# REGENIX_DRIVER_2.net
KiCad netlist of a schematic drawn in Altium Designer
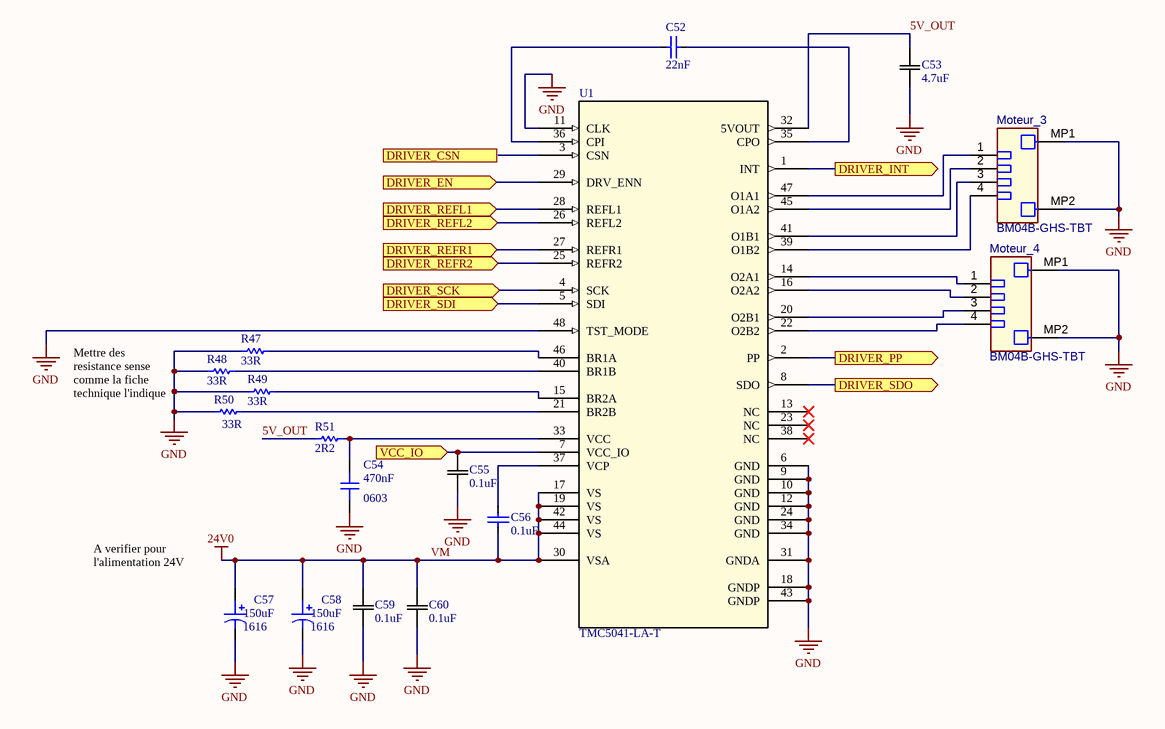
[diagram p0: REGENIX_DRIVER_2.SchDoc]

(export (version "E")
  (design (tool "Eeschema 10.0.6"))
  (components
    (comp (ref "C52")
      (value "22nF")
      (footprint "CAPACITOR-0603")
      (description "Capacitor-0603-0.22uF-25V-X7R")
      (libsource (lib "main_lib") (part "Capacitor-0603-0.22uF-25V-X7R"))
    )
    (comp (ref "C53")
      (value "4.7uF")
      (footprint "CAP_CL21_SAM")
      (description "CAP CER 4.7UF 25V X5R 0805  CL21A475KAQNNNE")
      (libsource (lib "CL21A475KAQNNNE") (part "CL21A475KAQNNNE"))
    )
    (comp (ref "C54")
      (value "470nF")
      (footprint "CAP_0603")
      (description "CAP - 0603")
      (fields (field (name "PACKAGE") "0603") (field (name "CREATEDBY") "Jonathan Bouchard"))
      (libsource (lib "S7CAS_LIB2023") (part "CAP - 0603"))
    )
    (comp (ref "C55")
      (value "0.1uF")
      (footprint "CAP_CL10_SAM")
      (description "CAP CER 0.1UF 50V X7R 0603 CL10B104KB8NNWC")
      (libsource (lib "CL10B104KB8NNWC") (part "CL10B104KB8NNWC"))
    )
    (comp (ref "C56")
      (value "0.1uF")
      (footprint "CAPACITOR-0603")
      (description "Capacitor-0603-0.22uF-25V-X7R")
      (libsource (lib "main_lib") (part "Capacitor-0603-0.22uF-25V-X7R"))
    )
    (comp (ref "C57")
      (value "150uF")
      (footprint "CAP_ALU_1616_vishay")
      (description "CAP - ALU 470uF 20% 50V - 1616")
      (fields
        (field (name "MFG") "Vishay Dale")
        (field (name "MFG PART NUMBER") "MAL214699108E3")
        (field (name "PACKAGE") "1616")
        (field (name "CREATEDBY") "Jonathan Bouchard")
      )
      (libsource (lib "S7CAS_LIB2023") (part "CAP_ALU_MAL214699108E3"))
    )
    (comp (ref "C58")
      (value "150uF")
      (footprint "CAP_ALU_1616_vishay")
      (description "CAP - ALU 470uF 20% 50V - 1616")
      (fields
        (field (name "MFG") "Vishay Dale")
        (field (name "MFG PART NUMBER") "MAL214699108E3")
        (field (name "PACKAGE") "1616")
        (field (name "CREATEDBY") "Jonathan Bouchard")
      )
      (libsource (lib "S7CAS_LIB2023") (part "CAP_ALU_MAL214699108E3"))
    )
    (comp (ref "C59")
      (value "0.1uF")
      (footprint "CAP_CL10_SAM")
      (description "CAP CER 0.1UF 50V X7R 0603 CL10B104KB8NNWC")
      (libsource (lib "CL10B104KB8NNWC") (part "CL10B104KB8NNWC"))
    )
    (comp (ref "C60")
      (value "0.1uF")
      (footprint "CAP_CL10_SAM")
      (description "CAP CER 0.1UF 50V X7R 0603 CL10B104KB8NNWC")
      (libsource (lib "CL10B104KB8NNWC") (part "CL10B104KB8NNWC"))
    )
    (comp (ref "Moteur_3")
      (value "BM04B-GHS-TBT")
      (footprint "JST-BM04B-GHS-TBT_V")
      (description "Header, Pitch 1.25 mm, 1 x 4 Position, Height 4.05 mm, -25 to 85 degC")
      (libsource (lib "Marylin Bechara") (part "CMP-00071-3"))
    )
    (comp (ref "Moteur_4")
      (value "BM04B-GHS-TBT")
      (footprint "JST-BM04B-GHS-TBT_V")
      (description "Header, Pitch 1.25 mm, 1 x 4 Position, Height 4.05 mm, -25 to 85 degC")
      (libsource (lib "Marylin Bechara") (part "CMP-00071-3"))
    )
    (comp (ref "R47")
      (value "33R")
      (footprint "RESISTOR-1206")
      (description "Resistor1206-33R")
      (fields (field (name "Comment") "SMT resistor"))
      (libsource (lib "main_lib") (part "Resistor1206-33R"))
    )
    (comp (ref "R48")
      (value "33R")
      (footprint "RESISTOR-1206")
      (description "Resistor1206-33R")
      (fields (field (name "Comment") "SMT resistor"))
      (libsource (lib "main_lib") (part "Resistor1206-33R"))
    )
    (comp (ref "R49")
      (value "33R")
      (footprint "RESISTOR-1206")
      (description "Resistor1206-33R")
      (fields (field (name "Comment") "SMT resistor"))
      (libsource (lib "main_lib") (part "Resistor1206-33R"))
    )
    (comp (ref "R50")
      (value "33R")
      (footprint "RESISTOR-1206")
      (description "Resistor1206-33R")
      (fields (field (name "Comment") "SMT resistor"))
      (libsource (lib "main_lib") (part "Resistor1206-33R"))
    )
    (comp (ref "R51")
      (value "2R2")
      (footprint "Resistor-0603")
      (description "Resistor0603-22R")
      (fields (field (name "Comment") "SMT resistor"))
      (libsource (lib "main_lib") (part "Resistor0603-22R"))
    )
    (comp (ref "U1")
      (value "TMC5041-LA-T")
      (footprint "QFN48_7X7_TRI")
      (description "No Description Available")
      (libsource (lib "TMC5041-LA-T") (part "TMC5041-LA-T"))
    )
  )
  (nets
    (net (code "1") (name "/5V_OUT") (class "Default")
      (node (ref "C53") (pin "2") (pinfunction "2_2") (pintype "passive"))
      (node (ref "R51") (pin "1") (pinfunction "1_1") (pintype "passive"))
      (node (ref "U1") (pin "32") (pinfunction "5VOUT_32") (pintype "output"))
    )
    (net (code "3") (name "/DRIVER_EN") (class "Default")
      (node (ref "U1") (pin "29") (pinfunction "DRV_ENN_29") (pintype "input"))
    )
    (net (code "4") (name "/DRIVER_INT") (class "Default")
      (node (ref "U1") (pin "1") (pinfunction "INT_1") (pintype "output"))
    )
    (net (code "5") (name "/DRIVER_PP") (class "Default")
      (node (ref "U1") (pin "2") (pinfunction "PP_2") (pintype "output"))
    )
    (net (code "6") (name "/DRIVER_REFL1") (class "Default")
      (node (ref "U1") (pin "28") (pinfunction "REFL1_28") (pintype "input"))
    )
    (net (code "7") (name "/DRIVER_REFL2") (class "Default")
      (node (ref "U1") (pin "26") (pinfunction "REFL2_26") (pintype "input"))
    )
    (net (code "8") (name "/DRIVER_REFR1") (class "Default")
      (node (ref "U1") (pin "27") (pinfunction "REFR1_27") (pintype "input"))
    )
    (net (code "9") (name "/DRIVER_REFR2") (class "Default")
      (node (ref "U1") (pin "25") (pinfunction "REFR2_25") (pintype "input"))
    )
    (net (code "10") (name "/DRIVER_SCK") (class "Default")
      (node (ref "U1") (pin "4") (pinfunction "SCK_4") (pintype "input"))
    )
    (net (code "11") (name "/DRIVER_SDI") (class "Default")
      (node (ref "U1") (pin "5") (pinfunction "SDI_5") (pintype "input"))
    )
    (net (code "12") (name "/DRIVER_SDO") (class "Default")
      (node (ref "U1") (pin "8") (pinfunction "SDO_8") (pintype "output"))
    )
    (net (code "13") (name "/VCC_IO") (class "Default")
      (node (ref "C55") (pin "2") (pinfunction "2_2") (pintype "passive"))
      (node (ref "U1") (pin "7") (pinfunction "VCC_IO_7") (pintype "power_in"))
    )
    (net (code "14") (name "24V0") (class "Default")
      (node (ref "C56") (pin "1") (pinfunction "1_1") (pintype "passive"))
      (node (ref "C57") (pin "1") (pinfunction "1_1") (pintype "passive"))
      (node (ref "C58") (pin "1") (pinfunction "1_1") (pintype "passive"))
      (node (ref "C59") (pin "2") (pinfunction "2_2") (pintype "passive"))
      (node (ref "C60") (pin "2") (pinfunction "2_2") (pintype "passive"))
      (node (ref "U1") (pin "17") (pinfunction "VS_17") (pintype "power_in"))
      (node (ref "U1") (pin "19") (pinfunction "VS_19") (pintype "power_in"))
      (node (ref "U1") (pin "30") (pinfunction "VSA_30") (pintype "power_in"))
      (node (ref "U1") (pin "42") (pinfunction "VS_42") (pintype "power_in"))
      (node (ref "U1") (pin "44") (pinfunction "VS_44") (pintype "power_in"))
    )
    (net (code "15") (name "GND") (class "Default")
      (node (ref "C53") (pin "1") (pinfunction "1_1") (pintype "passive"))
      (node (ref "C54") (pin "1") (pinfunction "1_1") (pintype "passive"))
      (node (ref "C55") (pin "1") (pinfunction "1_1") (pintype "passive"))
      (node (ref "C57") (pin "2") (pinfunction "2_2") (pintype "passive"))
      (node (ref "C58") (pin "2") (pinfunction "2_2") (pintype "passive"))
      (node (ref "C59") (pin "1") (pinfunction "1_1") (pintype "passive"))
      (node (ref "C60") (pin "1") (pinfunction "1_1") (pintype "passive"))
      (node (ref "Moteur_3") (pin "MP1") (pinfunction "MP1_MP1") (pintype "passive"))
      (node (ref "Moteur_3") (pin "MP2") (pinfunction "MP2_MP2") (pintype "passive"))
      (node (ref "Moteur_4") (pin "MP1") (pinfunction "MP1_MP1") (pintype "passive"))
      (node (ref "Moteur_4") (pin "MP2") (pinfunction "MP2_MP2") (pintype "passive"))
      (node (ref "R47") (pin "1") (pinfunction "1_1") (pintype "passive"))
      (node (ref "R48") (pin "1") (pinfunction "1_1") (pintype "passive"))
      (node (ref "R49") (pin "1") (pinfunction "1_1") (pintype "passive"))
      (node (ref "R50") (pin "1") (pinfunction "1_1") (pintype "passive"))
      (node (ref "U1") (pin "10") (pinfunction "GND_10") (pintype "power_in"))
      (node (ref "U1") (pin "11") (pinfunction "CLK_11") (pintype "input"))
      (node (ref "U1") (pin "12") (pinfunction "GND_12") (pintype "power_in"))
      (node (ref "U1") (pin "18") (pinfunction "GNDP_18") (pintype "power_in"))
      (node (ref "U1") (pin "24") (pinfunction "GND_24") (pintype "power_in"))
      (node (ref "U1") (pin "31") (pinfunction "GNDA_31") (pintype "power_in"))
      (node (ref "U1") (pin "34") (pinfunction "GND_34") (pintype "power_in"))
      (node (ref "U1") (pin "43") (pinfunction "GNDP_43") (pintype "power_in"))
      (node (ref "U1") (pin "48") (pinfunction "TST_MODE_48") (pintype "input"))
      (node (ref "U1") (pin "6") (pinfunction "GND_6") (pintype "power_in"))
      (node (ref "U1") (pin "9") (pinfunction "GND_9") (pintype "power_in"))
    )
    (net (code "16") (name "Net-(U1-BR1A)") (class "Default")
      (node (ref "R47") (pin "2") (pinfunction "2_2") (pintype "passive"))
      (node (ref "U1") (pin "46") (pinfunction "BR1A_46") (pintype "passive"))
    )
    (net (code "17") (name "Net-(U1-BR1B)") (class "Default")
      (node (ref "R48") (pin "2") (pinfunction "2_2") (pintype "passive"))
      (node (ref "U1") (pin "40") (pinfunction "BR1B_40") (pintype "passive"))
    )
    (net (code "18") (name "Net-(U1-BR2A)") (class "Default")
      (node (ref "R49") (pin "2") (pinfunction "2_2") (pintype "passive"))
      (node (ref "U1") (pin "15") (pinfunction "BR2A_15") (pintype "passive"))
    )
    (net (code "19") (name "Net-(U1-BR2B)") (class "Default")
      (node (ref "R50") (pin "2") (pinfunction "2_2") (pintype "passive"))
      (node (ref "U1") (pin "21") (pinfunction "BR2B_21") (pintype "passive"))
    )
    (net (code "20") (name "Net-(U1-CPI)") (class "Default")
      (node (ref "C52") (pin "1") (pinfunction "1_1") (pintype "passive"))
      (node (ref "U1") (pin "36") (pinfunction "CPI_36") (pintype "input"))
    )
    (net (code "21") (name "Net-(U1-CPO)") (class "Default")
      (node (ref "C52") (pin "2") (pinfunction "2_2") (pintype "passive"))
      (node (ref "U1") (pin "35") (pinfunction "CPO_35") (pintype "output"))
    )
    (net (code "22") (name "Net-(U1-O1A1)") (class "Default")
      (node (ref "Moteur_3") (pin "1") (pinfunction "1_1") (pintype "passive"))
      (node (ref "U1") (pin "47") (pinfunction "O1A1_47") (pintype "output"))
    )
    (net (code "23") (name "Net-(U1-O1A2)") (class "Default")
      (node (ref "Moteur_3") (pin "2") (pinfunction "2_2") (pintype "passive"))
      (node (ref "U1") (pin "45") (pinfunction "O1A2_45") (pintype "output"))
    )
    (net (code "24") (name "Net-(U1-O1B1)") (class "Default")
      (node (ref "Moteur_3") (pin "3") (pinfunction "3_3") (pintype "passive"))
      (node (ref "U1") (pin "41") (pinfunction "O1B1_41") (pintype "output"))
    )
    (net (code "25") (name "Net-(U1-O1B2)") (class "Default")
      (node (ref "Moteur_3") (pin "4") (pinfunction "4_4") (pintype "passive"))
      (node (ref "U1") (pin "39") (pinfunction "O1B2_39") (pintype "output"))
    )
    (net (code "26") (name "Net-(U1-O2A1)") (class "Default")
      (node (ref "Moteur_4") (pin "1") (pinfunction "1_1") (pintype "passive"))
      (node (ref "U1") (pin "14") (pinfunction "O2A1_14") (pintype "output"))
    )
    (net (code "27") (name "Net-(U1-O2A2)") (class "Default")
      (node (ref "Moteur_4") (pin "2") (pinfunction "2_2") (pintype "passive"))
      (node (ref "U1") (pin "16") (pinfunction "O2A2_16") (pintype "output"))
    )
    (net (code "28") (name "Net-(U1-O2B1)") (class "Default")
      (node (ref "Moteur_4") (pin "3") (pinfunction "3_3") (pintype "passive"))
      (node (ref "U1") (pin "20") (pinfunction "O2B1_20") (pintype "output"))
    )
    (net (code "29") (name "Net-(U1-O2B2)") (class "Default")
      (node (ref "Moteur_4") (pin "4") (pinfunction "4_4") (pintype "passive"))
      (node (ref "U1") (pin "22") (pinfunction "O2B2_22") (pintype "output"))
    )
    (net (code "30") (name "Net-(U1-VCC)") (class "Default")
      (node (ref "C54") (pin "2") (pinfunction "2_2") (pintype "passive"))
      (node (ref "R51") (pin "2") (pinfunction "2_2") (pintype "passive"))
      (node (ref "U1") (pin "33") (pinfunction "VCC_33") (pintype "power_in"))
    )
    (net (code "31") (name "Net-(U1-VCP)") (class "Default")
      (node (ref "C56") (pin "2") (pinfunction "2_2") (pintype "passive"))
      (node (ref "U1") (pin "37") (pinfunction "VCP_37") (pintype "power_in"))
    )
    (net (code "32") (name "unconnected-(U1-CSN-Pad3)") (class "Default")
      (node (ref "U1") (pin "3") (pinfunction "CSN_3") (pintype "input"))
    )
    (net (code "33") (name "unconnected-(U1-NC-Pad13)") (class "Default")
      (node (ref "U1") (pin "13") (pinfunction "NC_13") (pintype "passive+no_connect"))
    )
    (net (code "34") (name "unconnected-(U1-NC-Pad23)") (class "Default")
      (node (ref "U1") (pin "23") (pinfunction "NC_23") (pintype "passive+no_connect"))
    )
    (net (code "35") (name "unconnected-(U1-NC-Pad38)") (class "Default")
      (node (ref "U1") (pin "38") (pinfunction "NC_38") (pintype "passive+no_connect"))
    )
  )
)
